# rj45-breakout-10_0.net
KiCad netlist of a schematic drawn in EAGLE
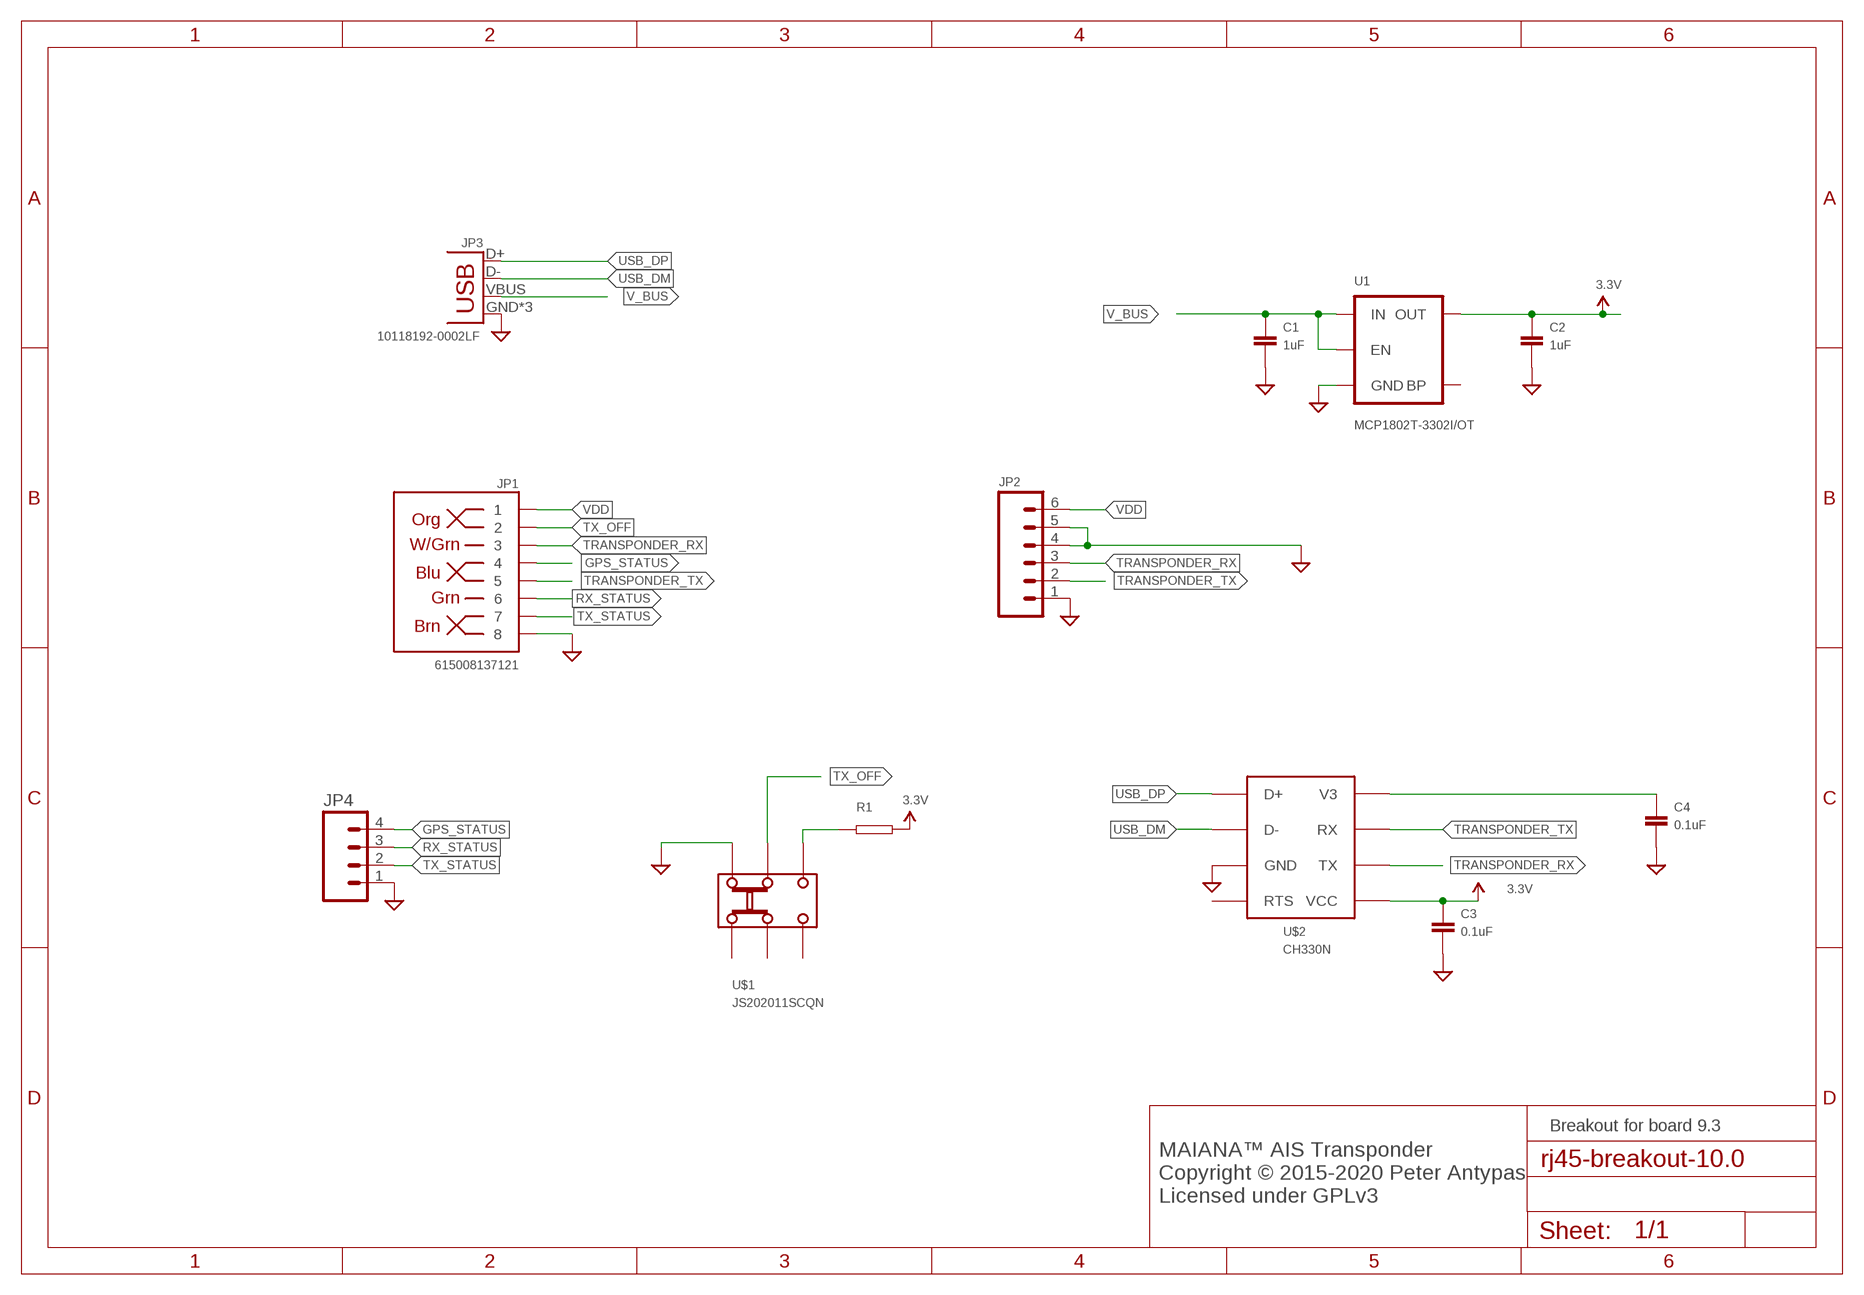
[diagram p0: schematic, sheet 1]

(export (version "E")
  (design (tool "Eeschema 10.0.6"))
  (components
    (comp (ref "C1")
      (value "1uF")
      (footprint "eagle-import:0603")
      (libsource (lib "eagle-import") (part "CAPACITOR0603"))
    )
    (comp (ref "C2")
      (value "1uF")
      (footprint "eagle-import:0603")
      (libsource (lib "eagle-import") (part "CAPACITOR0603"))
    )
    (comp (ref "C3")
      (value "0.1uF")
      (footprint "eagle-import:0603")
      (libsource (lib "eagle-import") (part "CAPACITOR0603"))
    )
    (comp (ref "C4")
      (value "0.1uF")
      (footprint "eagle-import:0603")
      (libsource (lib "eagle-import") (part "CAPACITOR0603"))
    )
    (comp (ref "JP1")
      (value "615008137121")
      (footprint "eagle-import:RJ45-8")
      (libsource (lib "eagle-import") (part "RJ45-8PTH"))
    )
    (comp (ref "JP2")
      (value "M06SILK_FEMALE_PTH")
      (footprint "eagle-import:1X06")
      (libsource (lib "eagle-import") (part "M06SILK_FEMALE_PTH"))
    )
    (comp (ref "JP3")
      (value "10118192-0002LF")
      (footprint "eagle-import:USB-MICROB")
      (libsource (lib "eagle-import") (part "USB-MICROB"))
    )
    (comp (ref "JP4")
      (value "M04PTH")
      (footprint "eagle-import:1X04")
      (libsource (lib "eagle-import") (part "M04PTH"))
    )
    (comp (ref "R1")
      (value "RESISTOR0603")
      (footprint "eagle-import:0603")
      (libsource (lib "eagle-import") (part "RESISTOR0603"))
    )
    (comp (ref "U$1")
      (value "JS202011SCQN")
      (footprint "eagle-import:DPDT-SMD")
      (libsource (lib "eagle-import") (part "JS202011SCQN"))
    )
    (comp (ref "U$2")
      (value "CH330N")
      (footprint "eagle-import:SOIC-8")
      (libsource (lib "eagle-import") (part "CH330N"))
    )
    (comp (ref "U1")
      (value "MCP1802T-3302I/OT")
      (footprint "eagle-import:SOT23-5")
      (libsource (lib "eagle-import") (part "V_REG_LDOSMD"))
    )
  )
  (nets
    (net (code "1") (name "3.3V") (class "Default")
      (node (ref "C2") (pin "P$1") (pinfunction "1_P$1") (pintype "passive"))
      (node (ref "C3") (pin "P$1") (pinfunction "1_P$1") (pintype "passive"))
      (node (ref "R1") (pin "P$2") (pinfunction "P$2_P$2") (pintype "passive"))
      (node (ref "U$2") (pin "5") (pinfunction "VCC_5") (pintype "bidirectional"))
      (node (ref "U1") (pin "5") (pinfunction "OUT_5") (pintype "passive"))
    )
    (net (code "2") (name "GND") (class "Default")
      (node (ref "C1") (pin "P$2") (pinfunction "2_P$2") (pintype "passive"))
      (node (ref "C2") (pin "P$2") (pinfunction "2_P$2") (pintype "passive"))
      (node (ref "C3") (pin "P$2") (pinfunction "2_P$2") (pintype "passive"))
      (node (ref "C4") (pin "P$2") (pinfunction "2_P$2") (pintype "passive"))
      (node (ref "JP1") (pin "8") (pinfunction "8_8") (pintype "bidirectional"))
      (node (ref "JP2") (pin "1") (pinfunction "1_1") (pintype "passive"))
      (node (ref "JP2") (pin "4") (pinfunction "4_4") (pintype "passive"))
      (node (ref "JP2") (pin "5") (pinfunction "5_5") (pintype "passive"))
      (node (ref "JP3") (pin "GND") (pinfunction "GND_GND") (pintype "bidirectional"))
      (node (ref "JP3") (pin "MT1") (pinfunction "GND_MT1") (pintype "bidirectional"))
      (node (ref "JP3") (pin "MT2") (pinfunction "GND_MT2") (pintype "bidirectional"))
      (node (ref "JP4") (pin "1") (pinfunction "1_1") (pintype "passive"))
      (node (ref "U$1") (pin "P$6") (pinfunction "P$6_P$6") (pintype "bidirectional"))
      (node (ref "U$2") (pin "3") (pinfunction "GND_3") (pintype "bidirectional"))
      (node (ref "U1") (pin "2") (pinfunction "GND_2") (pintype "input"))
    )
    (net (code "3") (name "GPS_STATUS") (class "Default")
      (node (ref "JP1") (pin "4") (pinfunction "4_4") (pintype "bidirectional"))
      (node (ref "JP4") (pin "4") (pinfunction "4_4") (pintype "passive"))
    )
    (net (code "4") (name "Net-(C4-1)") (class "Default")
      (node (ref "C4") (pin "P$1") (pinfunction "1_P$1") (pintype "passive"))
      (node (ref "U$2") (pin "8") (pinfunction "V3_8") (pintype "bidirectional"))
    )
    (net (code "5") (name "Net-(R1-PadP$1)") (class "Default")
      (node (ref "R1") (pin "P$1") (pinfunction "P$1_P$1") (pintype "passive"))
      (node (ref "U$1") (pin "P$4") (pinfunction "P$4_P$4") (pintype "bidirectional"))
    )
    (net (code "6") (name "RX_STATUS") (class "Default")
      (node (ref "JP1") (pin "6") (pinfunction "6_6") (pintype "bidirectional"))
      (node (ref "JP4") (pin "3") (pinfunction "3_3") (pintype "passive"))
    )
    (net (code "7") (name "TRANSPONDER_RX") (class "Default")
      (node (ref "JP1") (pin "3") (pinfunction "3_3") (pintype "bidirectional"))
      (node (ref "JP2") (pin "3") (pinfunction "3_3") (pintype "passive"))
      (node (ref "U$2") (pin "6") (pinfunction "TX_6") (pintype "bidirectional"))
    )
    (net (code "8") (name "TRANSPONDER_TX") (class "Default")
      (node (ref "JP1") (pin "5") (pinfunction "5_5") (pintype "bidirectional"))
      (node (ref "JP2") (pin "2") (pinfunction "2_2") (pintype "passive"))
      (node (ref "U$2") (pin "7") (pinfunction "RX_7") (pintype "bidirectional"))
    )
    (net (code "9") (name "TX_OFF") (class "Default")
      (node (ref "JP1") (pin "2") (pinfunction "2_2") (pintype "bidirectional"))
      (node (ref "U$1") (pin "P$5") (pinfunction "P$5_P$5") (pintype "bidirectional"))
    )
    (net (code "10") (name "TX_STATUS") (class "Default")
      (node (ref "JP1") (pin "7") (pinfunction "7_7") (pintype "bidirectional"))
      (node (ref "JP4") (pin "2") (pinfunction "2_2") (pintype "passive"))
    )
    (net (code "11") (name "USB_DM") (class "Default")
      (node (ref "JP3") (pin "D-") (pinfunction "D-_D-") (pintype "bidirectional"))
      (node (ref "U$2") (pin "2") (pinfunction "D-_2") (pintype "bidirectional"))
    )
    (net (code "12") (name "USB_DP") (class "Default")
      (node (ref "JP3") (pin "D+") (pinfunction "D+_D+") (pintype "bidirectional"))
      (node (ref "U$2") (pin "1") (pinfunction "D+_1") (pintype "bidirectional"))
    )
    (net (code "13") (name "VDD") (class "Default")
      (node (ref "JP1") (pin "1") (pinfunction "1_1") (pintype "bidirectional"))
      (node (ref "JP2") (pin "6") (pinfunction "6_6") (pintype "passive"))
    )
    (net (code "14") (name "V_BUS") (class "Default")
      (node (ref "C1") (pin "P$1") (pinfunction "1_P$1") (pintype "passive"))
      (node (ref "JP3") (pin "VBUS") (pinfunction "VBUS_VBUS") (pintype "bidirectional"))
      (node (ref "U1") (pin "1") (pinfunction "IN_1") (pintype "input"))
      (node (ref "U1") (pin "3") (pinfunction "EN_3") (pintype "input"))
    )
    (net (code "15") (name "unconnected-(U$1-PadP$1)") (class "Default")
      (node (ref "U$1") (pin "P$1") (pinfunction "P$1_P$1") (pintype "bidirectional"))
    )
    (net (code "16") (name "unconnected-(U$1-PadP$2)") (class "Default")
      (node (ref "U$1") (pin "P$2") (pinfunction "P$2_P$2") (pintype "bidirectional"))
    )
    (net (code "17") (name "unconnected-(U$1-PadP$3)") (class "Default")
      (node (ref "U$1") (pin "P$3") (pinfunction "P$3_P$3") (pintype "bidirectional"))
    )
    (net (code "18") (name "unconnected-(U$2-RTS-Pad4)") (class "Default")
      (node (ref "U$2") (pin "4") (pinfunction "RTS_4") (pintype "bidirectional"))
    )
    (net (code "19") (name "unconnected-(U1-BP-Pad4)") (class "Default")
      (node (ref "U1") (pin "4") (pinfunction "BP_4") (pintype "input"))
    )
  )
)
